# Input.net
KiCad netlist of a schematic drawn in Altium Designer
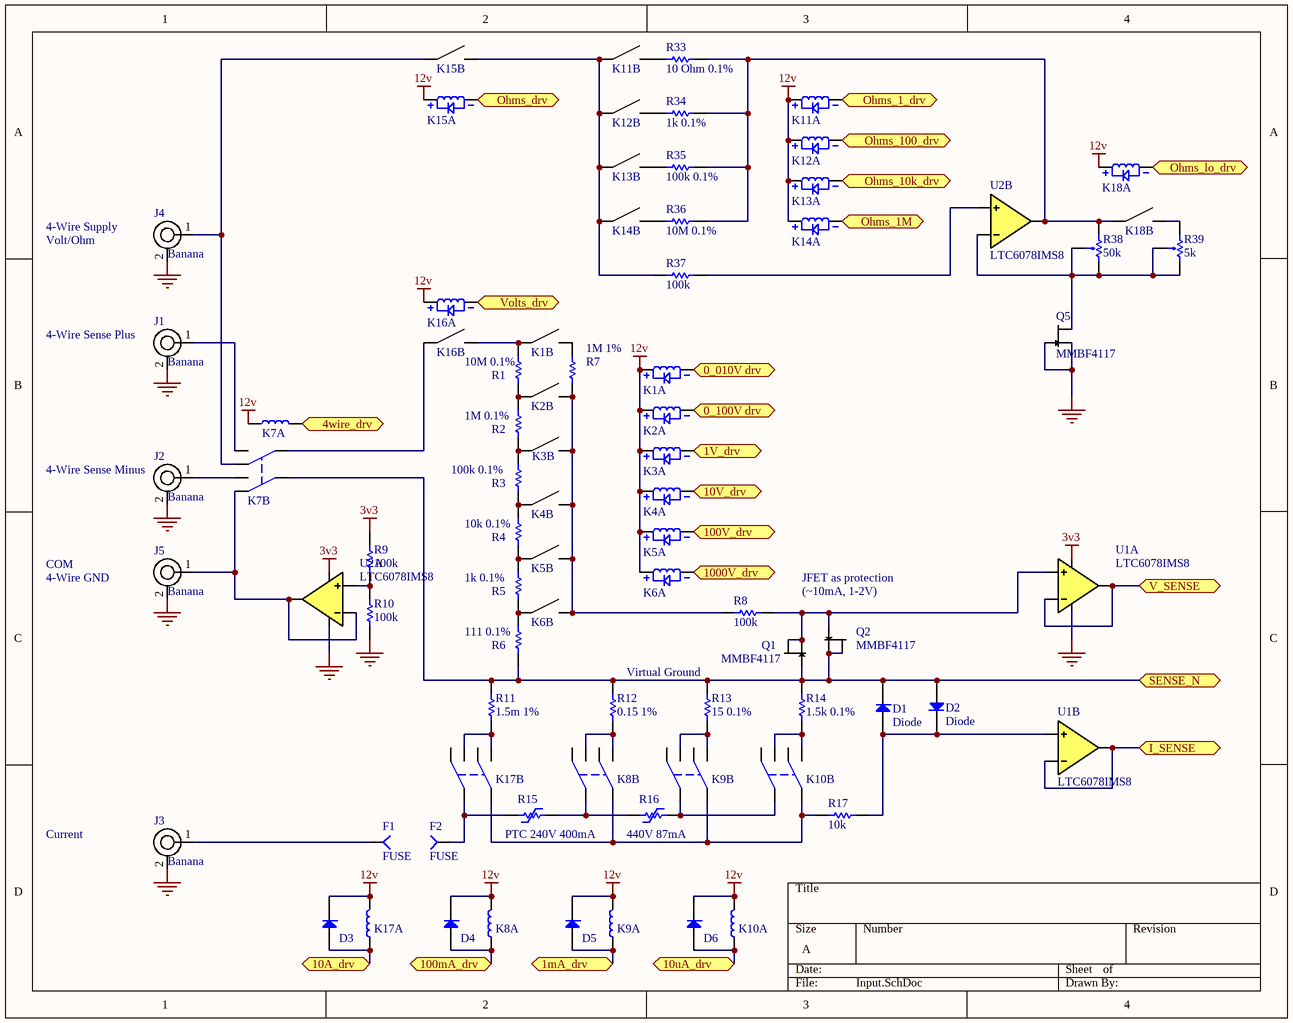
[diagram p0: Input.SchDoc]

(export (version "E")
  (design (tool "Eeschema 10.0.6"))
  (components
    (comp (ref "D1")
      (value "Diode")
      (footprint "SOD80")
      (description "DIODE GEN PURP 125V 200MA LL34")
      (libsource (lib "Schlib1") (part "Diode 125V 200mA"))
    )
    (comp (ref "D2")
      (value "Diode")
      (footprint "SOD80")
      (description "DIODE GEN PURP 125V 200MA LL34")
      (libsource (lib "Schlib1") (part "Diode 125V 200mA"))
    )
    (comp (ref "D3")
      (value "Diode")
      (footprint "SOD80")
      (description "DIODE GEN PURP 100V 200MA LL34")
      (libsource (lib "Schlib1") (part "Diode 100V 200mA"))
    )
    (comp (ref "D4")
      (value "Diode")
      (footprint "SOD80")
      (description "DIODE GEN PURP 100V 200MA LL34")
      (libsource (lib "Schlib1") (part "Diode 100V 200mA"))
    )
    (comp (ref "D5")
      (value "Diode")
      (footprint "SOD80")
      (description "DIODE GEN PURP 100V 200MA LL34")
      (libsource (lib "Schlib1") (part "Diode 100V 200mA"))
    )
    (comp (ref "D6")
      (value "Diode")
      (footprint "SOD80")
      (description "DIODE GEN PURP 100V 200MA LL34")
      (libsource (lib "Schlib1") (part "Diode 100V 200mA"))
    )
    (comp (ref "F1")
      (value "FUSE")
      (footprint "FUSE CLIP")
      (description "FUSE CLIP CARTRIDGE 30A PCB")
      (libsource (lib "Schlib1") (part "FUSE CLIP"))
    )
    (comp (ref "F2")
      (value "FUSE")
      (footprint "FUSE CLIP")
      (description "FUSE CLIP CARTRIDGE 30A PCB")
      (libsource (lib "Schlib1") (part "FUSE CLIP"))
    )
    (comp (ref "J1")
      (value "Banana")
      (footprint "FCR7350")
      (description "SOCKET, PCB, 4MM, R/A, S16N-PC, YEL")
      (libsource (lib "Schlib1") (part "Banana Jack"))
    )
    (comp (ref "J2")
      (value "Banana")
      (footprint "FCR7350")
      (description "SOCKET, PCB, 4MM, R/A, S16N-PC, YEL")
      (libsource (lib "Schlib1") (part "Banana Jack"))
    )
    (comp (ref "J3")
      (value "Banana")
      (footprint "FCR7350")
      (description "SOCKET, PCB, 4MM, R/A, S16N-PC, YEL")
      (libsource (lib "Schlib1") (part "Banana Jack"))
    )
    (comp (ref "J4")
      (value "Banana")
      (footprint "FCR7350")
      (description "SOCKET, PCB, 4MM, R/A, S16N-PC, YEL")
      (libsource (lib "Schlib1") (part "Banana Jack"))
    )
    (comp (ref "J5")
      (value "Banana")
      (footprint "FCR7350")
      (description "SOCKET, PCB, 4MM, R/A, S16N-PC, YEL")
      (libsource (lib "Schlib1") (part "Banana Jack"))
    )
    (comp (ref "K1")
      (value "Relay Reed SPST 1000V / 500mA 12V")
      (footprint "Coto 9104-12-11")
      (description "RELAY REED SPST 500MA 12V")
      (libsource (lib "Schlib1") (part "Relay Reed SPST 1000V / 500mA 12V"))
    )
    (comp (ref "K2")
      (value "Relay Reed SPST 500mA 12V")
      (footprint "HE3621A")
      (description "RELAY REED SPST 500MA 12V")
      (libsource (lib "Schlib1") (part "Relay Reed SPST 500mA 12V"))
    )
    (comp (ref "K3")
      (value "Relay Reed SPST 500mA 12V")
      (footprint "HE3621A")
      (description "RELAY REED SPST 500MA 12V")
      (libsource (lib "Schlib1") (part "Relay Reed SPST 500mA 12V"))
    )
    (comp (ref "K4")
      (value "Relay Reed SPST 500mA 12V")
      (footprint "HE3621A")
      (description "RELAY REED SPST 500MA 12V")
      (libsource (lib "Schlib1") (part "Relay Reed SPST 500mA 12V"))
    )
    (comp (ref "K5")
      (value "Relay Reed SPST 500mA 12V")
      (footprint "HE3621A")
      (description "RELAY REED SPST 500MA 12V")
      (libsource (lib "Schlib1") (part "Relay Reed SPST 500mA 12V"))
    )
    (comp (ref "K6")
      (value "Relay Reed SPST 500mA 12V")
      (footprint "HE3621A")
      (description "RELAY REED SPST 500MA 12V")
      (libsource (lib "Schlib1") (part "Relay Reed SPST 500mA 12V"))
    )
    (comp (ref "K7")
      (value "Relay DPDT 15A 12V")
      (footprint "K10-pcb")
      (description "RELAY GEN PURPOSE DPDT 15A 12V")
      (libsource (lib "Schlib1") (part "Relay DPDT 15A 12V"))
    )
    (comp (ref "K8")
      (value "Relay DPDT 2A 12V")
      (footprint "EE2-12NU")
      (description "RELAY GEN PURPOSE DPDT 2A 12V")
      (libsource (lib "Schlib1") (part "Relay DPDT 2A 12V"))
    )
    (comp (ref "K9")
      (value "Relay DPDT 2A 12V")
      (footprint "EE2-12NU")
      (description "RELAY GEN PURPOSE DPDT 2A 12V")
      (libsource (lib "Schlib1") (part "Relay DPDT 2A 12V"))
    )
    (comp (ref "K10")
      (value "Relay DPDT 2A 12V")
      (footprint "EE2-12NU")
      (description "RELAY GEN PURPOSE DPDT 2A 12V")
      (libsource (lib "Schlib1") (part "Relay DPDT 2A 12V"))
    )
    (comp (ref "K11")
      (value "Relay Reed SPST 500mA 12V")
      (footprint "HE3621A")
      (description "RELAY REED SPST 500MA 12V")
      (libsource (lib "Schlib1") (part "Relay Reed SPST 500mA 12V"))
    )
    (comp (ref "K12")
      (value "Relay Reed SPST 500mA 12V")
      (footprint "HE3621A")
      (description "RELAY REED SPST 500MA 12V")
      (libsource (lib "Schlib1") (part "Relay Reed SPST 500mA 12V"))
    )
    (comp (ref "K13")
      (value "Relay Reed SPST 500mA 12V")
      (footprint "HE3621A")
      (description "RELAY REED SPST 500MA 12V")
      (libsource (lib "Schlib1") (part "Relay Reed SPST 500mA 12V"))
    )
    (comp (ref "K14")
      (value "Relay Reed SPST 500mA 12V")
      (footprint "HE3621A")
      (description "RELAY REED SPST 500MA 12V")
      (libsource (lib "Schlib1") (part "Relay Reed SPST 500mA 12V"))
    )
    (comp (ref "K15")
      (value "Relay Reed SPST 500mA 12V")
      (footprint "HE3621A")
      (description "RELAY REED SPST 500MA 12V")
      (libsource (lib "Schlib1") (part "Relay Reed SPST 500mA 12V"))
    )
    (comp (ref "K16")
      (value "Relay Reed SPST 1000V / 500mA 12V")
      (footprint "Coto 9104-12-11")
      (description "RELAY REED SPST 500MA 12V")
      (libsource (lib "Schlib1") (part "Relay Reed SPST 1000V / 500mA 12V"))
    )
    (comp (ref "K17")
      (value "Relay DPDT 15A 12V")
      (footprint "K10-pcb")
      (description "RELAY GEN PURPOSE DPDT 15A 12V")
      (libsource (lib "Schlib1") (part "Relay DPDT 15A 12V"))
    )
    (comp (ref "K18")
      (value "Relay Reed SPST 500mA 12V")
      (footprint "HE3621A")
      (description "RELAY REED SPST 500MA 12V")
      (libsource (lib "Schlib1") (part "Relay Reed SPST 500mA 12V"))
    )
    (comp (ref "Q1")
      (value "MMBF4117")
      (footprint "SOT_23")
      (description "JFET N-CH 40V 0.225W SOT23")
      (libsource (lib "Schlib1") (part "MMBF4117"))
    )
    (comp (ref "Q2")
      (value "MMBF4117")
      (footprint "SOT_23")
      (description "JFET N-CH 40V 0.225W SOT23")
      (libsource (lib "Schlib1") (part "MMBF4117"))
    )
    (comp (ref "Q5")
      (value "MMBF4117")
      (footprint "SOT_23")
      (description "JFET N-CH 40V 0.225W SOT23")
      (libsource (lib "Schlib1") (part "MMBF4117"))
    )
    (comp (ref "R1")
      (value "10M 0.1%")
      (footprint "R2010")
      (description "RES SMD 10M OHM 0.1% 1W 2010")
      (libsource (lib "Schlib1") (part "10M 2010 0.1%"))
    )
    (comp (ref "R2")
      (value "1M 0.1%")
      (footprint "R1206")
      (description "RES SMD 1M OHM 0.1% 1/4W 1206")
      (libsource (lib "Schlib1") (part "1M 1206 0.1%"))
    )
    (comp (ref "R3")
      (value "100k 0.1%")
      (footprint "R0805")
      (description "RES SMD 100K OHM 0.1% 1/8W 0805")
      (libsource (lib "Schlib1") (part "100k 0805 0.1%"))
    )
    (comp (ref "R4")
      (value "10k 0.1%")
      (footprint "R0603")
      (description "RES SMD 10K OHM 0.1% 1/10W 0603")
      (libsource (lib "Schlib1") (part "10k 0603 0.1%"))
    )
    (comp (ref "R5")
      (value "1k 0.1%")
      (footprint "R0603")
      (description "RES SMD 1K OHM 0.1% 1/10W 0603")
      (libsource (lib "Schlib1") (part "1k 0603 0.1%"))
    )
    (comp (ref "R6")
      (value "111 0.1%")
      (footprint "R0402")
      (description "RES 111 OHM 0.1% 1/10W 0402")
      (libsource (lib "Schlib1") (part "111 0402 0.1%"))
    )
    (comp (ref "R7")
      (value "1M 1%")
      (footprint "R2512")
      (description "CHV2512-FX-1004ELF")
      (libsource (lib "Schlib1") (part "1M 2512 1%"))
    )
    (comp (ref "R8")
      (value "100k")
      (footprint "R0603")
      (description "RES SMD 100K OHM 5% 1/10W 0603")
      (libsource (lib "Schlib1") (part "100k 0603 5%"))
    )
    (comp (ref "R9")
      (value "100k")
      (footprint "R0603")
      (description "RES SMD 100K OHM 5% 1/10W 0603")
      (libsource (lib "Schlib1") (part "100k 0603 5%"))
    )
    (comp (ref "R10")
      (value "100k")
      (footprint "R0603")
      (description "RES SMD 100K OHM 5% 1/10W 0603")
      (libsource (lib "Schlib1") (part "100k 0603 5%"))
    )
    (comp (ref "R11")
      (value "1.5m 1%")
      (footprint "R2512")
      (description "RES 0.0015 OHM 1% 3W 2512")
      (libsource (lib "Schlib1") (part "1.5m 2512 1%"))
    )
    (comp (ref "R12")
      (value "0.15 1%")
      (footprint "R2010")
      (description "RES 0.15 OHM 1% 1W 2010")
      (libsource (lib "Schlib1") (part "0.15 2010 1%"))
    )
    (comp (ref "R13")
      (value "15 0.1%")
      (footprint "R0805")
      (description "RES SMD 15 OHM 0.1% 1/8W 0805")
      (libsource (lib "Schlib1") (part "15 0805 0.1%"))
    )
    (comp (ref "R14")
      (value "1.5k 0.1%")
      (footprint "R0603")
      (description "RES SMD 1.5K OHM 0.1% 1/5W 0603")
      (libsource (lib "Schlib1") (part "1.5k 0603 0.1%"))
    )
    (comp (ref "R15")
      (value "PTC 240V 400mA")
      (footprint "0ZRE0040FF1A")
      (description "PTC RESET FUSE 240V 400MA RADIAL")
      (libsource (lib "Schlib1") (part "PTC 240V 400mA"))
    )
    (comp (ref "R16")
      (value "440V 87mA")
      (footprint "B59751C0120A070")
      (description "PTC RESET FUSE 440V 87MA RADIAL")
      (libsource (lib "Schlib1") (part "PTC 440V 87mA"))
    )
    (comp (ref "R17")
      (value "10k")
      (footprint "R0603")
      (description "RES SMD 10K OHM 5% 1/10W 0603")
      (libsource (lib "Schlib1") (part "10k 0603 5%"))
    )
    (comp (ref "R33")
      (value "10 Ohm 0.1%")
      (footprint "R0603")
      (description "RES SMD 10 OHM 0.1% 1/10W 0603")
      (libsource (lib "Schlib1") (part "10 Ohm 0603 0.1%"))
    )
    (comp (ref "R34")
      (value "1k 0.1%")
      (footprint "R0603")
      (description "RES SMD 1K OHM 0.1% 1/10W 0603")
      (libsource (lib "Schlib1") (part "1k 0603 0.1%"))
    )
    (comp (ref "R35")
      (value "100k 0.1%")
      (footprint "R0805")
      (description "RES SMD 100K OHM 0.1% 1/8W 0805")
      (libsource (lib "Schlib1") (part "100k 0805 0.1%"))
    )
    (comp (ref "R36")
      (value "10M 0.1%")
      (footprint "R1206")
      (description "RES 10M OHM 0.1% 1/3W 1206")
      (libsource (lib "Schlib1") (part "10M 1206 0.1%"))
    )
    (comp (ref "R37")
      (value "100k")
      (footprint "R0603")
      (description "RES SMD 100K OHM 5% 1/10W 0603")
      (libsource (lib "Schlib1") (part "100k 0603 5%"))
    )
    (comp (ref "R38")
      (value "50k")
      (footprint "PV36")
      (description "TRIMMER 50K OHM 0.5W TH")
      (libsource (lib "Schlib1") (part "TRIMMER 50K"))
    )
    (comp (ref "R39")
      (value "5k")
      (footprint "PV36")
      (description "TRIMMER 5K OHM 0.5W TH")
      (libsource (lib "Schlib1") (part "TRIMMER 5K"))
    )
    (comp (ref "U1")
      (value "LTC6078IMS8")
      (footprint "8MSOP")
      (libsource (lib "Schlib1") (part "LTC6078IMS8"))
    )
    (comp (ref "U2")
      (value "LTC6078IMS8")
      (footprint "8MSOP")
      (libsource (lib "Schlib1") (part "LTC6078IMS8"))
    )
  )
  (nets
    (net (code "1") (name "/0_010V drv") (class "Default")
      (node (ref "K1") (pin "5") (pinfunction "5_5") (pintype "passive"))
    )
    (net (code "2") (name "/0_100V drv") (class "Default")
      (node (ref "K2") (pin "3") (pinfunction "3_3") (pintype "passive"))
    )
    (net (code "3") (name "/1V_drv") (class "Default")
      (node (ref "K3") (pin "3") (pinfunction "3_3") (pintype "passive"))
    )
    (net (code "4") (name "/1mA_drv") (class "Default")
      (node (ref "D5") (pin "1") (pinfunction "A_1") (pintype "passive"))
      (node (ref "K9") (pin "1") (pinfunction "1_1") (pintype "passive"))
    )
    (net (code "5") (name "/4wire_drv") (class "Default")
      (node (ref "K7") (pin "8") (pinfunction "8_8") (pintype "passive"))
    )
    (net (code "6") (name "/10A_drv") (class "Default")
      (node (ref "D3") (pin "1") (pinfunction "A_1") (pintype "passive"))
      (node (ref "K17") (pin "7") (pinfunction "7_7") (pintype "passive"))
    )
    (net (code "7") (name "/10V_drv") (class "Default")
      (node (ref "K4") (pin "3") (pinfunction "3_3") (pintype "passive"))
    )
    (net (code "8") (name "/10uA_drv") (class "Default")
      (node (ref "D6") (pin "1") (pinfunction "A_1") (pintype "passive"))
      (node (ref "K10") (pin "1") (pinfunction "1_1") (pintype "passive"))
    )
    (net (code "9") (name "/100V_drv") (class "Default")
      (node (ref "K5") (pin "3") (pinfunction "3_3") (pintype "passive"))
    )
    (net (code "10") (name "/100mA_drv") (class "Default")
      (node (ref "D4") (pin "1") (pinfunction "A_1") (pintype "passive"))
      (node (ref "K8") (pin "1") (pinfunction "1_1") (pintype "passive"))
    )
    (net (code "11") (name "/1000V_drv") (class "Default")
      (node (ref "K6") (pin "3") (pinfunction "3_3") (pintype "passive"))
    )
    (net (code "12") (name "/I_SENSE") (class "Default")
      (node (ref "U1") (pin "6") (pinfunction "6_6") (pintype "passive"))
      (node (ref "U1") (pin "7") (pinfunction "7_7") (pintype "passive"))
    )
    (net (code "13") (name "/Ohms_1M") (class "Default")
      (node (ref "K14") (pin "3") (pinfunction "3_3") (pintype "passive"))
    )
    (net (code "14") (name "/Ohms_1_drv") (class "Default")
      (node (ref "K11") (pin "3") (pinfunction "3_3") (pintype "passive"))
    )
    (net (code "15") (name "/Ohms_10k_drv") (class "Default")
      (node (ref "K13") (pin "3") (pinfunction "3_3") (pintype "passive"))
    )
    (net (code "16") (name "/Ohms_100_drv") (class "Default")
      (node (ref "K12") (pin "3") (pinfunction "3_3") (pintype "passive"))
    )
    (net (code "17") (name "/Ohms_drv") (class "Default")
      (node (ref "K15") (pin "3") (pinfunction "3_3") (pintype "passive"))
    )
    (net (code "18") (name "/Ohms_lo_drv") (class "Default")
      (node (ref "K18") (pin "3") (pinfunction "3_3") (pintype "passive"))
    )
    (net (code "19") (name "/SENSE_N") (class "Default")
      (node (ref "D1") (pin "2") (pinfunction "K_2") (pintype "passive"))
      (node (ref "D2") (pin "1") (pinfunction "A_1") (pintype "passive"))
      (node (ref "K7") (pin "6") (pinfunction "6_6") (pintype "passive"))
      (node (ref "Q1") (pin "3") (pinfunction "3_3") (pintype "passive"))
      (node (ref "Q2") (pin "1") (pinfunction "1_1") (pintype "passive"))
      (node (ref "Q2") (pin "2") (pinfunction "2_2") (pintype "passive"))
      (node (ref "R11") (pin "2") (pinfunction "2_2") (pintype "passive"))
      (node (ref "R12") (pin "2") (pinfunction "2_2") (pintype "passive"))
      (node (ref "R13") (pin "2") (pinfunction "2_2") (pintype "passive"))
      (node (ref "R14") (pin "2") (pinfunction "2_2") (pintype "passive"))
      (node (ref "R6") (pin "1") (pinfunction "1_1") (pintype "passive"))
    )
    (net (code "20") (name "/V_SENSE") (class "Default")
      (node (ref "U1") (pin "1") (pinfunction "1_1") (pintype "passive"))
      (node (ref "U1") (pin "2") (pinfunction "2_2") (pintype "passive"))
    )
    (net (code "21") (name "/Volts_drv") (class "Default")
      (node (ref "K16") (pin "5") (pinfunction "5_5") (pintype "passive"))
    )
    (net (code "22") (name "3v3") (class "Default")
      (node (ref "R9") (pin "2") (pinfunction "2_2") (pintype "passive"))
      (node (ref "U1") (pin "8") (pinfunction "8_8") (pintype "passive"))
      (node (ref "U2") (pin "8") (pinfunction "8_8") (pintype "passive"))
    )
    (net (code "23") (name "12v") (class "Default")
      (node (ref "D3") (pin "2") (pinfunction "K_2") (pintype "passive"))
      (node (ref "D4") (pin "2") (pinfunction "K_2") (pintype "passive"))
      (node (ref "D5") (pin "2") (pinfunction "K_2") (pintype "passive"))
      (node (ref "D6") (pin "2") (pinfunction "K_2") (pintype "passive"))
      (node (ref "K1") (pin "3") (pinfunction "3_3") (pintype "passive"))
      (node (ref "K10") (pin "12") (pinfunction "12_12") (pintype "passive"))
      (node (ref "K11") (pin "2") (pinfunction "2_2") (pintype "passive"))
      (node (ref "K12") (pin "2") (pinfunction "2_2") (pintype "passive"))
      (node (ref "K13") (pin "2") (pinfunction "2_2") (pintype "passive"))
      (node (ref "K14") (pin "2") (pinfunction "2_2") (pintype "passive"))
      (node (ref "K15") (pin "2") (pinfunction "2_2") (pintype "passive"))
      (node (ref "K16") (pin "3") (pinfunction "3_3") (pintype "passive"))
      (node (ref "K17") (pin "8") (pinfunction "8_8") (pintype "passive"))
      (node (ref "K18") (pin "2") (pinfunction "2_2") (pintype "passive"))
      (node (ref "K2") (pin "2") (pinfunction "2_2") (pintype "passive"))
      (node (ref "K3") (pin "2") (pinfunction "2_2") (pintype "passive"))
      (node (ref "K4") (pin "2") (pinfunction "2_2") (pintype "passive"))
      (node (ref "K5") (pin "2") (pinfunction "2_2") (pintype "passive"))
      (node (ref "K6") (pin "2") (pinfunction "2_2") (pintype "passive"))
      (node (ref "K7") (pin "7") (pinfunction "7_7") (pintype "passive"))
      (node (ref "K8") (pin "12") (pinfunction "12_12") (pintype "passive"))
      (node (ref "K9") (pin "12") (pinfunction "12_12") (pintype "passive"))
    )
    (net (code "24") (name "GND") (class "Default")
      (node (ref "J1") (pin "2") (pinfunction "2_2") (pintype "passive"))
      (node (ref "J2") (pin "2") (pinfunction "2_2") (pintype "passive"))
      (node (ref "J3") (pin "2") (pinfunction "2_2") (pintype "passive"))
      (node (ref "J4") (pin "2") (pinfunction "2_2") (pintype "passive"))
      (node (ref "J5") (pin "2") (pinfunction "2_2") (pintype "passive"))
      (node (ref "Q5") (pin "1") (pinfunction "1_1") (pintype "passive"))
      (node (ref "Q5") (pin "3") (pinfunction "3_3") (pintype "passive"))
      (node (ref "R10") (pin "1") (pinfunction "1_1") (pintype "passive"))
      (node (ref "U1") (pin "4") (pinfunction "4_4") (pintype "passive"))
      (node (ref "U2") (pin "4") (pinfunction "4_4") (pintype "passive"))
    )
    (net (code "25") (name "Net-(D1-A)") (class "Default")
      (node (ref "D1") (pin "1") (pinfunction "A_1") (pintype "passive"))
      (node (ref "D2") (pin "2") (pinfunction "K_2") (pintype "passive"))
      (node (ref "R17") (pin "2") (pinfunction "2_2") (pintype "passive"))
      (node (ref "U1") (pin "5") (pinfunction "5_5") (pintype "passive"))
    )
    (net (code "26") (name "Net-(F1-Pad1)") (class "Default")
      (node (ref "F1") (pin "1") (pinfunction "1_1") (pintype "passive"))
      (node (ref "J3") (pin "1") (pinfunction "1_1") (pintype "passive"))
    )
    (net (code "27") (name "Net-(F2-Pad1)") (class "Default")
      (node (ref "F2") (pin "1") (pinfunction "1_1") (pintype "passive"))
      (node (ref "K17") (pin "6") (pinfunction "6_6") (pintype "passive"))
      (node (ref "R15") (pin "1") (pinfunction "1_1") (pintype "passive"))
    )
    (net (code "28") (name "Net-(J1-Pad1)") (class "Default")
      (node (ref "J1") (pin "1") (pinfunction "1_1") (pintype "passive"))
      (node (ref "K7") (pin "3") (pinfunction "3_3") (pintype "passive"))
    )
    (net (code "29") (name "Net-(J2-Pad1)") (class "Default")
      (node (ref "J2") (pin "1") (pinfunction "1_1") (pintype "passive"))
      (node (ref "K7") (pin "4") (pinfunction "4_4") (pintype "passive"))
    )
    (net (code "30") (name "Net-(J4-Pad1)") (class "Default")
      (node (ref "J4") (pin "1") (pinfunction "1_1") (pintype "passive"))
      (node (ref "K15") (pin "1") (pinfunction "1_1") (pintype "passive"))
      (node (ref "K7") (pin "1") (pinfunction "1_1") (pintype "passive"))
    )
    (net (code "31") (name "Net-(J5-Pad1)") (class "Default")
      (node (ref "J5") (pin "1") (pinfunction "1_1") (pintype "passive"))
      (node (ref "K7") (pin "2") (pinfunction "2_2") (pintype "passive"))
      (node (ref "U2") (pin "1") (pinfunction "1_1") (pintype "passive"))
      (node (ref "U2") (pin "2") (pinfunction "2_2") (pintype "passive"))
    )
    (net (code "32") (name "Net-(K1-Pad1)") (class "Default")
      (node (ref "K1") (pin "1") (pinfunction "1_1") (pintype "passive"))
      (node (ref "K16") (pin "7") (pinfunction "7_7") (pintype "passive"))
      (node (ref "R1") (pin "2") (pinfunction "2_2") (pintype "passive"))
    )
    (net (code "33") (name "Net-(K1-Pad7)") (class "Default")
      (node (ref "K1") (pin "7") (pinfunction "7_7") (pintype "passive"))
      (node (ref "R7") (pin "2") (pinfunction "2_2") (pintype "passive"))
    )
    (net (code "34") (name "Net-(K2-Pad1)") (class "Default")
      (node (ref "K2") (pin "1") (pinfunction "1_1") (pintype "passive"))
      (node (ref "R1") (pin "1") (pinfunction "1_1") (pintype "passive"))
      (node (ref "R2") (pin "2") (pinfunction "2_2") (pintype "passive"))
    )
    (net (code "35") (name "Net-(K2-Pad4)") (class "Default")
      (node (ref "K2") (pin "4") (pinfunction "4_4") (pintype "passive"))
      (node (ref "K3") (pin "4") (pinfunction "4_4") (pintype "passive"))
      (node (ref "K4") (pin "4") (pinfunction "4_4") (pintype "passive"))
      (node (ref "K5") (pin "4") (pinfunction "4_4") (pintype "passive"))
      (node (ref "K6") (pin "4") (pinfunction "4_4") (pintype "passive"))
      (node (ref "R7") (pin "1") (pinfunction "1_1") (pintype "passive"))
      (node (ref "R8") (pin "1") (pinfunction "1_1") (pintype "passive"))
    )
    (net (code "36") (name "Net-(K3-Pad1)") (class "Default")
      (node (ref "K3") (pin "1") (pinfunction "1_1") (pintype "passive"))
      (node (ref "R2") (pin "1") (pinfunction "1_1") (pintype "passive"))
      (node (ref "R3") (pin "2") (pinfunction "2_2") (pintype "passive"))
    )
    (net (code "37") (name "Net-(K4-Pad1)") (class "Default")
      (node (ref "K4") (pin "1") (pinfunction "1_1") (pintype "passive"))
      (node (ref "R3") (pin "1") (pinfunction "1_1") (pintype "passive"))
      (node (ref "R4") (pin "2") (pinfunction "2_2") (pintype "passive"))
    )
    (net (code "38") (name "Net-(K5-Pad1)") (class "Default")
      (node (ref "K5") (pin "1") (pinfunction "1_1") (pintype "passive"))
      (node (ref "R4") (pin "1") (pinfunction "1_1") (pintype "passive"))
      (node (ref "R5") (pin "2") (pinfunction "2_2") (pintype "passive"))
    )
    (net (code "39") (name "Net-(K6-Pad1)") (class "Default")
      (node (ref "K6") (pin "1") (pinfunction "1_1") (pintype "passive"))
      (node (ref "R5") (pin "1") (pinfunction "1_1") (pintype "passive"))
      (node (ref "R6") (pin "2") (pinfunction "2_2") (pintype "passive"))
    )
    (net (code "40") (name "Net-(K8-Pad4)") (class "Default")
      (node (ref "K8") (pin "4") (pinfunction "4_4") (pintype "passive"))
      (node (ref "R15") (pin "2") (pinfunction "2_2") (pintype "passive"))
      (node (ref "R16") (pin "1") (pinfunction "1_1") (pintype "passive"))
    )
    (net (code "41") (name "Net-(K8-Pad5)") (class "Default")
      (node (ref "K8") (pin "5") (pinfunction "5_5") (pintype "passive"))
      (node (ref "K8") (pin "8") (pinfunction "8_8") (pintype "passive"))
      (node (ref "R12") (pin "1") (pinfunction "1_1") (pintype "passive"))
    )
    (net (code "42") (name "Net-(K9-Pad5)") (class "Default")
      (node (ref "K9") (pin "5") (pinfunction "5_5") (pintype "passive"))
      (node (ref "K9") (pin "8") (pinfunction "8_8") (pintype "passive"))
      (node (ref "R13") (pin "1") (pinfunction "1_1") (pintype "passive"))
    )
    (net (code "43") (name "Net-(K10-Pad4)") (class "Default")
      (node (ref "K10") (pin "4") (pinfunction "4_4") (pintype "passive"))
      (node (ref "K9") (pin "4") (pinfunction "4_4") (pintype "passive"))
      (node (ref "R16") (pin "2") (pinfunction "2_2") (pintype "passive"))
    )
    (net (code "44") (name "Net-(K10-Pad5)") (class "Default")
      (node (ref "K10") (pin "5") (pinfunction "5_5") (pintype "passive"))
      (node (ref "K10") (pin "8") (pinfunction "8_8") (pintype "passive"))
      (node (ref "R14") (pin "1") (pinfunction "1_1") (pintype "passive"))
    )
    (net (code "45") (name "Net-(K10-Pad9)") (class "Default")
      (node (ref "K10") (pin "9") (pinfunction "9_9") (pintype "passive"))
      (node (ref "K17") (pin "5") (pinfunction "5_5") (pintype "passive"))
      (node (ref "K8") (pin "9") (pinfunction "9_9") (pintype "passive"))
      (node (ref "K9") (pin "9") (pinfunction "9_9") (pintype "passive"))
      (node (ref "R17") (pin "1") (pinfunction "1_1") (pintype "passive"))
    )
    (net (code "46") (name "Net-(K11-Pad1)") (class "Default")
      (node (ref "K11") (pin "1") (pinfunction "1_1") (pintype "passive"))
      (node (ref "K12") (pin "1") (pinfunction "1_1") (pintype "passive"))
      (node (ref "K13") (pin "1") (pinfunction "1_1") (pintype "passive"))
      (node (ref "K14") (pin "1") (pinfunction "1_1") (pintype "passive"))
      (node (ref "K15") (pin "4") (pinfunction "4_4") (pintype "passive"))
      (node (ref "R37") (pin "1") (pinfunction "1_1") (pintype "passive"))
    )
    (net (code "47") (name "Net-(K11-Pad4)") (class "Default")
      (node (ref "K11") (pin "4") (pinfunction "4_4") (pintype "passive"))
      (node (ref "R33") (pin "1") (pinfunction "1_1") (pintype "passive"))
    )
    (net (code "48") (name "Net-(K12-Pad4)") (class "Default")
      (node (ref "K12") (pin "4") (pinfunction "4_4") (pintype "passive"))
      (node (ref "R34") (pin "1") (pinfunction "1_1") (pintype "passive"))
    )
    (net (code "49") (name "Net-(K13-Pad4)") (class "Default")
      (node (ref "K13") (pin "4") (pinfunction "4_4") (pintype "passive"))
      (node (ref "R35") (pin "1") (pinfunction "1_1") (pintype "passive"))
    )
    (net (code "50") (name "Net-(K14-Pad4)") (class "Default")
      (node (ref "K14") (pin "4") (pinfunction "4_4") (pintype "passive"))
      (node (ref "R36") (pin "1") (pinfunction "1_1") (pintype "passive"))
    )
    (net (code "51") (name "Net-(K16-Pad1)") (class "Default")
      (node (ref "K16") (pin "1") (pinfunction "1_1") (pintype "passive"))
      (node (ref "K7") (pin "5") (pinfunction "5_5") (pintype "passive"))
    )
    (net (code "52") (name "Net-(K17-Pad3)") (class "Default")
      (node (ref "K17") (pin "3") (pinfunction "3_3") (pintype "passive"))
      (node (ref "K17") (pin "4") (pinfunction "4_4") (pintype "passive"))
      (node (ref "R11") (pin "1") (pinfunction "1_1") (pintype "passive"))
    )
    (net (code "53") (name "Net-(K18-Pad1)") (class "Default")
      (node (ref "K18") (pin "1") (pinfunction "1_1") (pintype "passive"))
      (node (ref "R33") (pin "2") (pinfunction "2_2") (pintype "passive"))
      (node (ref "R34") (pin "2") (pinfunction "2_2") (pintype "passive"))
      (node (ref "R35") (pin "2") (pinfunction "2_2") (pintype "passive"))
      (node (ref "R36") (pin "2") (pinfunction "2_2") (pintype "passive"))
      (node (ref "R38") (pin "3") (pinfunction "3_3") (pintype "passive"))
      (node (ref "U2") (pin "7") (pinfunction "7_7") (pintype "passive"))
    )
    (net (code "54") (name "Net-(K18-Pad4)") (class "Default")
      (node (ref "K18") (pin "4") (pinfunction "4_4") (pintype "passive"))
      (node (ref "R39") (pin "3") (pinfunction "3_3") (pintype "passive"))
    )
    (net (code "55") (name "Net-(Q1-Pad1)") (class "Default")
      (node (ref "Q1") (pin "1") (pinfunction "1_1") (pintype "passive"))
      (node (ref "Q1") (pin "2") (pinfunction "2_2") (pintype "passive"))
      (node (ref "Q2") (pin "3") (pinfunction "3_3") (pintype "passive"))
      (node (ref "R8") (pin "2") (pinfunction "2_2") (pintype "passive"))
      (node (ref "U1") (pin "3") (pinfunction "3_3") (pintype "passive"))
    )
    (net (code "56") (name "Net-(Q5-Pad2)") (class "Default")
      (node (ref "Q5") (pin "2") (pinfunction "2_2") (pintype "passive"))
      (node (ref "R38") (pin "1") (pinfunction "1_1") (pintype "passive"))
      (node (ref "R38") (pin "2") (pinfunction "2_2") (pintype "passive"))
      (node (ref "R39") (pin "1") (pinfunction "1_1") (pintype "passive"))
      (node (ref "R39") (pin "2") (pinfunction "2_2") (pintype "passive"))
      (node (ref "U2") (pin "6") (pinfunction "6_6") (pintype "passive"))
    )
    (net (code "57") (name "Net-(R10-Pad2)") (class "Default")
      (node (ref "R10") (pin "2") (pinfunction "2_2") (pintype "passive"))
      (node (ref "R9") (pin "1") (pinfunction "1_1") (pintype "passive"))
      (node (ref "U2") (pin "3") (pinfunction "3_3") (pintype "passive"))
    )
    (net (code "58") (name "Net-(R37-Pad2)") (class "Default")
      (node (ref "R37") (pin "2") (pinfunction "2_2") (pintype "passive"))
      (node (ref "U2") (pin "5") (pinfunction "5_5") (pintype "passive"))
    )
    (net (code "59") (name "unconnected-(K8-Pad3)") (class "Default")
      (node (ref "K8") (pin "3") (pinfunction "3_3") (pintype "passive"))
    )
    (net (code "60") (name "unconnected-(K8-Pad10)") (class "Default")
      (node (ref "K8") (pin "10") (pinfunction "10_10") (pintype "passive"))
    )
    (net (code "61") (name "unconnected-(K9-Pad3)") (class "Default")
      (node (ref "K9") (pin "3") (pinfunction "3_3") (pintype "passive"))
    )
    (net (code "62") (name "unconnected-(K9-Pad10)") (class "Default")
      (node (ref "K9") (pin "10") (pinfunction "10_10") (pintype "passive"))
    )
    (net (code "63") (name "unconnected-(K10-Pad3)") (class "Default")
      (node (ref "K10") (pin "3") (pinfunction "3_3") (pintype "passive"))
    )
    (net (code "64") (name "unconnected-(K10-Pad10)") (class "Default")
      (node (ref "K10") (pin "10") (pinfunction "10_10") (pintype "passive"))
    )
    (net (code "65") (name "unconnected-(K17-Pad1)") (class "Default")
      (node (ref "K17") (pin "1") (pinfunction "1_1") (pintype "passive"))
    )
    (net (code "66") (name "unconnected-(K17-Pad2)") (class "Default")
      (node (ref "K17") (pin "2") (pinfunction "2_2") (pintype "passive"))
    )
  )
)
